# Declan.net
KiCad netlist of a schematic drawn in EAGLE
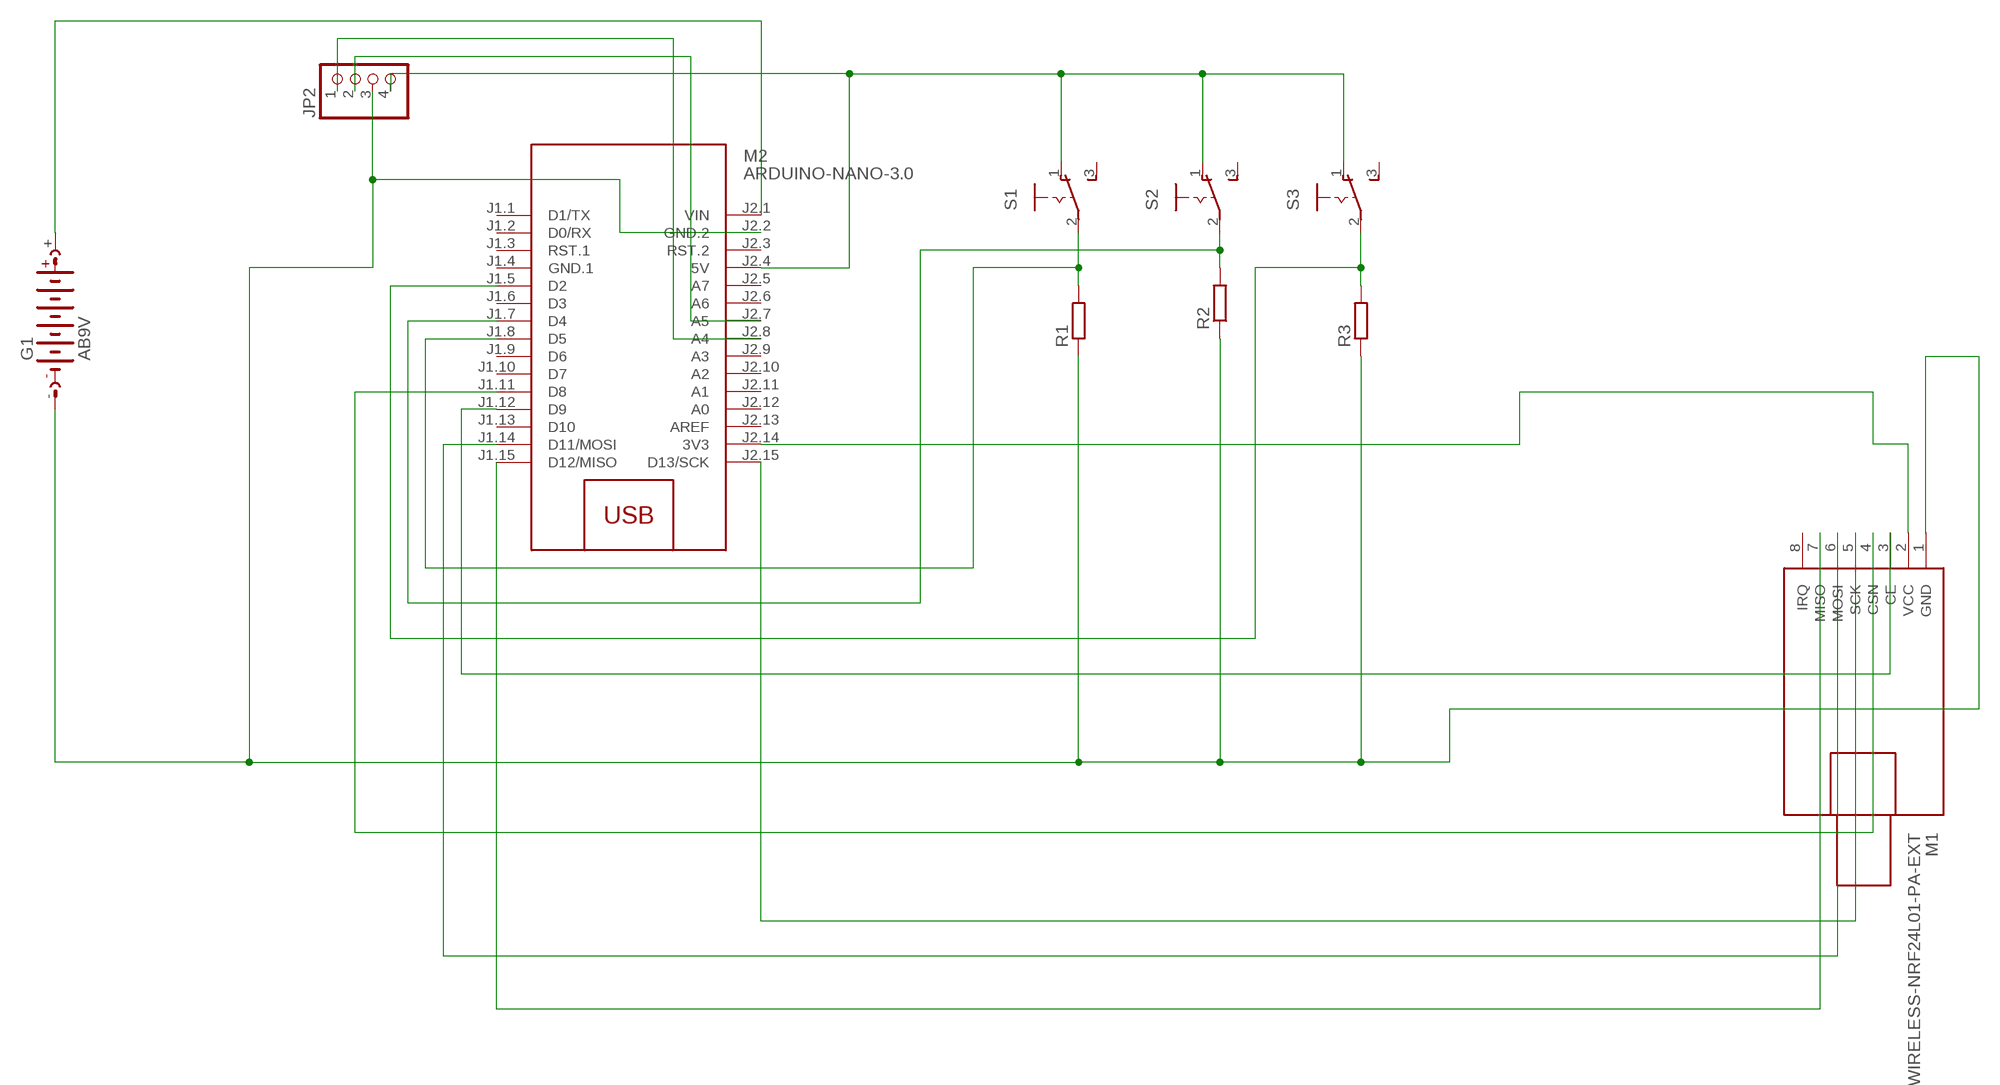
[diagram p0: schematic, sheet 1]

(export (version "E")
  (design (tool "Eeschema 10.0.6"))
  (components
    (comp (ref "G1")
      (value "AB9V")
      (footprint "eagle-import:AB9V")
      (libsource (lib "eagle-import") (part "AB9V"))
    )
    (comp (ref "JP2")
      (value "PINHD-1X4")
      (footprint "eagle-import:1X04")
      (libsource (lib "eagle-import") (part "PINHD-1X4"))
    )
    (comp (ref "M1")
      (value "WIRELESS-NRF24L01-PA-EXT")
      (footprint "eagle-import:WIRELESS-NRF24L01-PA-EXT")
      (libsource (lib "eagle-import") (part "WIRELESS-NRF24L01-PA-EXT"))
    )
    (comp (ref "M2")
      (value "ARDUINO-NANO-3.0")
      (footprint "eagle-import:ARDUINO-NANO-3.0")
      (libsource (lib "eagle-import") (part "ARDUINO-NANO-3.0"))
    )
    (comp (ref "R1")
      (value "R-EU_0207/10")
      (footprint "eagle-import:0207_10")
      (libsource (lib "eagle-import") (part "R-EU_0207/10"))
    )
    (comp (ref "R2")
      (value "R-EU_0207/10")
      (footprint "eagle-import:0207_10")
      (libsource (lib "eagle-import") (part "R-EU_0207/10"))
    )
    (comp (ref "R3")
      (value "R-EU_0207/10")
      (footprint "eagle-import:0207_10")
      (libsource (lib "eagle-import") (part "R-EU_0207/10"))
    )
    (comp (ref "S1")
      (value "255SB")
      (footprint "eagle-import:255SB")
      (libsource (lib "eagle-import") (part "255SB"))
    )
    (comp (ref "S2")
      (value "255SB")
      (footprint "eagle-import:255SB")
      (libsource (lib "eagle-import") (part "255SB"))
    )
    (comp (ref "S3")
      (value "255SB")
      (footprint "eagle-import:255SB")
      (libsource (lib "eagle-import") (part "255SB"))
    )
  )
  (nets
    (net (code "1") (name "/GND.1") (class "Default")
      (node (ref "M2") (pin "J1.4") (pinfunction "GND.1_J1.4") (pintype "power_in"))
    )
    (net (code "2") (name "Net-(M1-CE)") (class "Default")
      (node (ref "M1") (pin "3") (pinfunction "CE_3") (pintype "bidirectional"))
      (node (ref "M2") (pin "J1.12") (pinfunction "D9_J1.12") (pintype "bidirectional"))
    )
    (net (code "3") (name "Net-(M1-CSN)") (class "Default")
      (node (ref "M1") (pin "4") (pinfunction "CSN_4") (pintype "bidirectional"))
      (node (ref "M2") (pin "J1.11") (pinfunction "D8_J1.11") (pintype "bidirectional"))
    )
    (net (code "4") (name "Net-(M1-GND)") (class "Default")
      (node (ref "G1") (pin "-") (pinfunction "-_-") (pintype "passive"))
      (node (ref "JP2") (pin "3") (pinfunction "3_3") (pintype "passive"))
      (node (ref "M1") (pin "1") (pinfunction "GND_1") (pintype "power_in"))
      (node (ref "M2") (pin "J2.2") (pinfunction "GND.2_J2.2") (pintype "power_in"))
      (node (ref "R1") (pin "1") (pinfunction "1_1") (pintype "passive"))
      (node (ref "R2") (pin "1") (pinfunction "1_1") (pintype "passive"))
      (node (ref "R3") (pin "1") (pinfunction "1_1") (pintype "passive"))
    )
    (net (code "5") (name "Net-(M1-MISO)") (class "Default")
      (node (ref "M1") (pin "7") (pinfunction "MISO_7") (pintype "bidirectional"))
      (node (ref "M2") (pin "J1.15") (pinfunction "D12/MISO_J1.15") (pintype "bidirectional"))
    )
    (net (code "6") (name "Net-(M1-MOSI)") (class "Default")
      (node (ref "M1") (pin "6") (pinfunction "MOSI_6") (pintype "bidirectional"))
      (node (ref "M2") (pin "J1.14") (pinfunction "D11/MOSI_J1.14") (pintype "bidirectional"))
    )
    (net (code "7") (name "Net-(M1-SCK)") (class "Default")
      (node (ref "M1") (pin "5") (pinfunction "SCK_5") (pintype "bidirectional"))
      (node (ref "M2") (pin "J2.15") (pinfunction "D13/SCK_J2.15") (pintype "bidirectional"))
    )
    (net (code "8") (name "Net-(M1-VCC)") (class "Default")
      (node (ref "M1") (pin "2") (pinfunction "VCC_2") (pintype "power_in"))
      (node (ref "M2") (pin "J2.14") (pinfunction "3V3_J2.14") (pintype "power_in"))
    )
    (net (code "9") (name "Net-(M2-5V)") (class "Default")
      (node (ref "JP2") (pin "4") (pinfunction "4_4") (pintype "passive"))
      (node (ref "M2") (pin "J2.4") (pinfunction "5V_J2.4") (pintype "power_in"))
      (node (ref "S1") (pin "1") (pinfunction "O_1") (pintype "passive"))
      (node (ref "S2") (pin "1") (pinfunction "O_1") (pintype "passive"))
      (node (ref "S3") (pin "1") (pinfunction "O_1") (pintype "passive"))
    )
    (net (code "10") (name "Net-(M2-A4)") (class "Default")
      (node (ref "JP2") (pin "1") (pinfunction "1_1") (pintype "passive"))
      (node (ref "M2") (pin "J2.8") (pinfunction "A4_J2.8") (pintype "bidirectional"))
    )
    (net (code "11") (name "Net-(M2-A5)") (class "Default")
      (node (ref "JP2") (pin "2") (pinfunction "2_2") (pintype "passive"))
      (node (ref "M2") (pin "J2.7") (pinfunction "A5_J2.7") (pintype "bidirectional"))
    )
    (net (code "12") (name "Net-(M2-D2)") (class "Default")
      (node (ref "M2") (pin "J1.5") (pinfunction "D2_J1.5") (pintype "bidirectional"))
      (node (ref "R3") (pin "2") (pinfunction "2_2") (pintype "passive"))
      (node (ref "S3") (pin "2") (pinfunction "P_2") (pintype "passive"))
    )
    (net (code "13") (name "Net-(M2-D4)") (class "Default")
      (node (ref "M2") (pin "J1.7") (pinfunction "D4_J1.7") (pintype "bidirectional"))
      (node (ref "R2") (pin "2") (pinfunction "2_2") (pintype "passive"))
      (node (ref "S2") (pin "2") (pinfunction "P_2") (pintype "passive"))
    )
    (net (code "14") (name "Net-(M2-D5)") (class "Default")
      (node (ref "M2") (pin "J1.8") (pinfunction "D5_J1.8") (pintype "bidirectional"))
      (node (ref "R1") (pin "2") (pinfunction "2_2") (pintype "passive"))
      (node (ref "S1") (pin "2") (pinfunction "P_2") (pintype "passive"))
    )
    (net (code "15") (name "Net-(M2-VIN)") (class "Default")
      (node (ref "G1") (pin "+") (pinfunction "+_+") (pintype "passive"))
      (node (ref "M2") (pin "J2.1") (pinfunction "VIN_J2.1") (pintype "power_in"))
    )
    (net (code "16") (name "unconnected-(M1-IRQ-Pad8)") (class "Default")
      (node (ref "M1") (pin "8") (pinfunction "IRQ_8") (pintype "bidirectional"))
    )
    (net (code "17") (name "unconnected-(M2-A0-PadJ2.12)") (class "Default")
      (node (ref "M2") (pin "J2.12") (pinfunction "A0_J2.12") (pintype "bidirectional"))
    )
    (net (code "18") (name "unconnected-(M2-A1-PadJ2.11)") (class "Default")
      (node (ref "M2") (pin "J2.11") (pinfunction "A1_J2.11") (pintype "bidirectional"))
    )
    (net (code "19") (name "unconnected-(M2-A2-PadJ2.10)") (class "Default")
      (node (ref "M2") (pin "J2.10") (pinfunction "A2_J2.10") (pintype "bidirectional"))
    )
    (net (code "20") (name "unconnected-(M2-A3-PadJ2.9)") (class "Default")
      (node (ref "M2") (pin "J2.9") (pinfunction "A3_J2.9") (pintype "bidirectional"))
    )
    (net (code "21") (name "unconnected-(M2-A6-PadJ2.6)") (class "Default")
      (node (ref "M2") (pin "J2.6") (pinfunction "A6_J2.6") (pintype "bidirectional"))
    )
    (net (code "22") (name "unconnected-(M2-A7-PadJ2.5)") (class "Default")
      (node (ref "M2") (pin "J2.5") (pinfunction "A7_J2.5") (pintype "bidirectional"))
    )
    (net (code "23") (name "unconnected-(M2-AREF-PadJ2.13)") (class "Default")
      (node (ref "M2") (pin "J2.13") (pinfunction "AREF_J2.13") (pintype "bidirectional"))
    )
    (net (code "24") (name "unconnected-(M2-D0{slash}RX-PadJ1.2)") (class "Default")
      (node (ref "M2") (pin "J1.2") (pinfunction "D0/RX_J1.2") (pintype "bidirectional"))
    )
    (net (code "25") (name "unconnected-(M2-D1{slash}TX-PadJ1.1)") (class "Default")
      (node (ref "M2") (pin "J1.1") (pinfunction "D1/TX_J1.1") (pintype "bidirectional"))
    )
    (net (code "26") (name "unconnected-(M2-D3-PadJ1.6)") (class "Default")
      (node (ref "M2") (pin "J1.6") (pinfunction "D3_J1.6") (pintype "bidirectional"))
    )
    (net (code "27") (name "unconnected-(M2-D6-PadJ1.9)") (class "Default")
      (node (ref "M2") (pin "J1.9") (pinfunction "D6_J1.9") (pintype "bidirectional"))
    )
    (net (code "28") (name "unconnected-(M2-D7-PadJ1.10)") (class "Default")
      (node (ref "M2") (pin "J1.10") (pinfunction "D7_J1.10") (pintype "bidirectional"))
    )
    (net (code "29") (name "unconnected-(M2-D10-PadJ1.13)") (class "Default")
      (node (ref "M2") (pin "J1.13") (pinfunction "D10_J1.13") (pintype "bidirectional"))
    )
    (net (code "30") (name "unconnected-(M2-RST.1-PadJ1.3)") (class "Default")
      (node (ref "M2") (pin "J1.3") (pinfunction "RST.1_J1.3") (pintype "bidirectional"))
    )
    (net (code "31") (name "unconnected-(M2-RST.2-PadJ2.3)") (class "Default")
      (node (ref "M2") (pin "J2.3") (pinfunction "RST.2_J2.3") (pintype "bidirectional"))
    )
    (net (code "32") (name "unconnected-(S1-S-Pad3)") (class "Default")
      (node (ref "S1") (pin "3") (pinfunction "S_3") (pintype "passive"))
    )
    (net (code "33") (name "unconnected-(S2-S-Pad3)") (class "Default")
      (node (ref "S2") (pin "3") (pinfunction "S_3") (pintype "passive"))
    )
    (net (code "34") (name "unconnected-(S3-S-Pad3)") (class "Default")
      (node (ref "S3") (pin "3") (pinfunction "S_3") (pintype "passive"))
    )
  )
)
